# CONNECTROS.net
KiCad netlist of a schematic drawn in Altium Designer
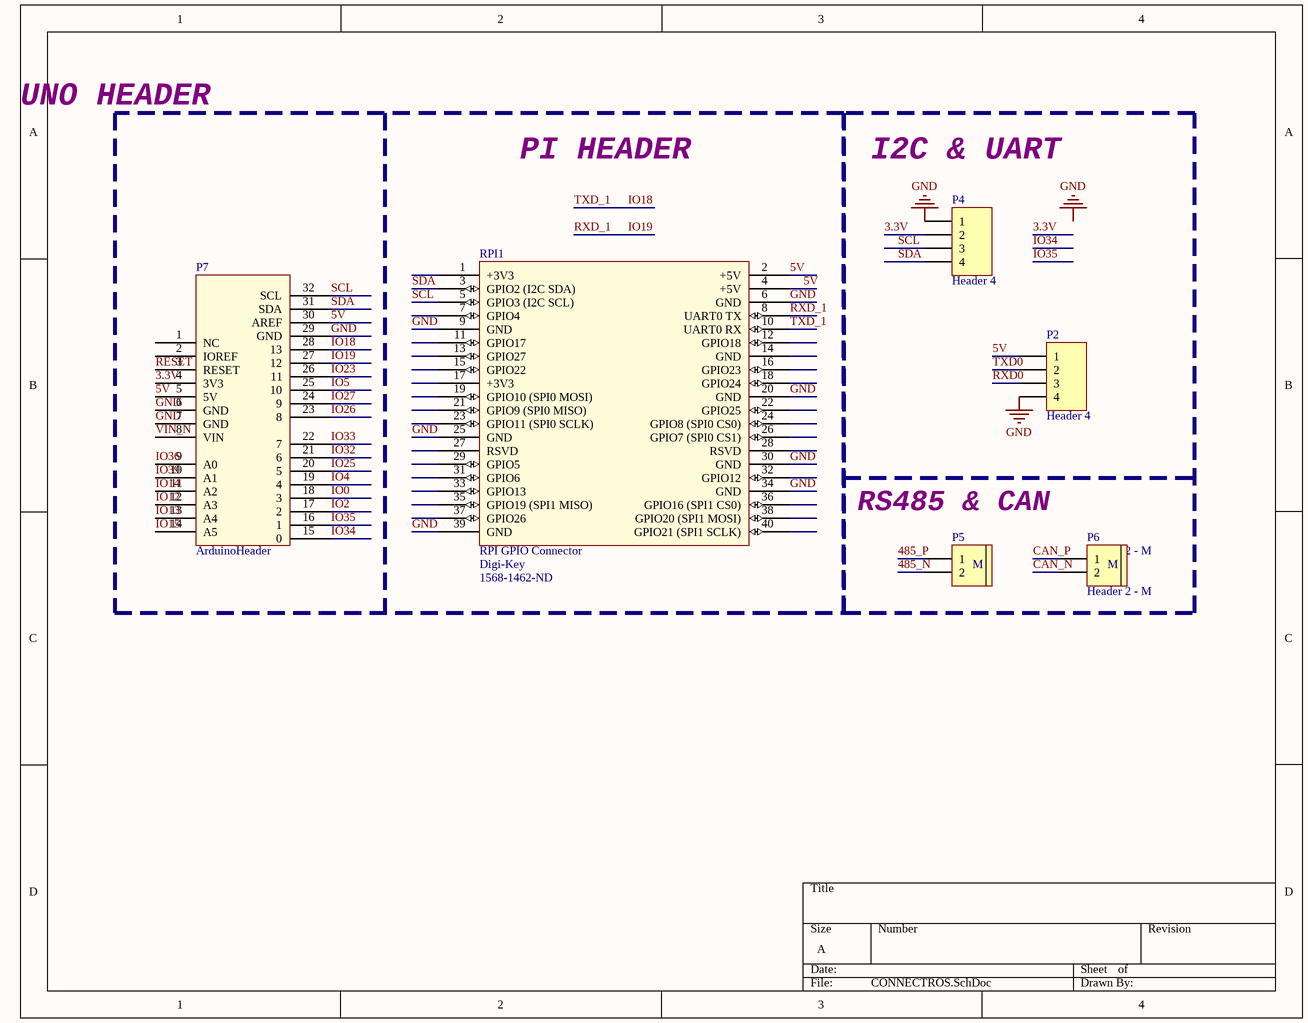
[diagram p0: CONNECTROS.SchDoc]

(export (version "E")
  (design (tool "Eeschema 10.0.6"))
  (components
    (comp (ref "P2")
      (value "Header 4")
      (footprint "HDR1X4")
      (description "Header, 4-Pin")
      (fields (field (name "PUBLISHER") "Altium Limited"))
      (libsource (lib "Miscellaneous Connectors") (part "Header 4"))
    )
    (comp (ref "P4")
      (value "Header 4")
      (footprint "CONN-TH_XH2.54-4AW")
      (description "Header, 4-Pin")
      (fields (field (name "PUBLISHER") "Altium Limited"))
      (libsource (lib "Miscellaneous Connectors") (part "Header 4"))
    )
    (comp (ref "P5")
      (value "Header 2 - M")
      (footprint "Medium - Header 2")
      (description "Header, 2-Pin, Medium")
      (fields (field (name "PUBLISHER") "Altium Limited"))
      (libsource (lib "My Library") (part "Header 2 - M"))
    )
    (comp (ref "P6")
      (value "Header 2 - M")
      (footprint "Medium - Header 2")
      (description "Header, 2-Pin, Medium")
      (fields (field (name "PUBLISHER") "Altium Limited"))
      (libsource (lib "My Library") (part "Header 2 - M"))
    )
    (comp (ref "P7")
      (value "ArduinoHeader")
      (footprint "ArduinoClone2")
      (libsource (lib "electronpowered") (part "ArduinoHeader"))
    )
    (comp (ref "RPI1")
      (value "RPI GPIO Connector")
      (footprint "rpi")
      (description "GPIO Header for Raspberry Pi A+/B+/Pi 2/Pi 3 - 2x20")
      (fields
        (field (name "MANUFACTURER") "SparkFun Electronics")
        (field (name "MANUFACTURER PART NUMBER") "PRT-14017")
        (field (name "SUPPLIER 1") "Digi-Key")
        (field (name "SUPPLIER PART NUMBER 1") "1568-1462-ND")
      )
      (libsource (lib "rpi") (part "rpi connector"))
    )
  )
  (nets
    (net (code "1") (name "/3.3V") (class "Default")
      (node (ref "P4") (pin "2") (pinfunction "2_2") (pintype "passive"))
      (node (ref "P7") (pin "4") (pinfunction "3V3_4") (pintype "passive"))
    )
    (net (code "2") (name "/5V") (class "Default")
      (node (ref "P2") (pin "1") (pinfunction "1_1") (pintype "passive"))
      (node (ref "P7") (pin "30") (pinfunction "AREF_30") (pintype "passive"))
      (node (ref "P7") (pin "5") (pinfunction "5V_5") (pintype "passive"))
      (node (ref "RPI1") (pin "2") (pinfunction "+5V_2") (pintype "power_in"))
      (node (ref "RPI1") (pin "4") (pinfunction "+5V_4") (pintype "power_in"))
    )
    (net (code "3") (name "/485_N") (class "Default")
      (node (ref "P5") (pin "2") (pinfunction "2_2") (pintype "passive"))
    )
    (net (code "4") (name "/485_P") (class "Default")
      (node (ref "P5") (pin "1") (pinfunction "1_1") (pintype "passive"))
    )
    (net (code "5") (name "/CAN_N") (class "Default")
      (node (ref "P6") (pin "2") (pinfunction "2_2") (pintype "passive"))
    )
    (net (code "6") (name "/CAN_P") (class "Default")
      (node (ref "P6") (pin "1") (pinfunction "1_1") (pintype "passive"))
    )
    (net (code "7") (name "/IO0") (class "Default")
      (node (ref "P7") (pin "18") (pinfunction "3_18") (pintype "passive"))
    )
    (net (code "8") (name "/IO2") (class "Default")
      (node (ref "P7") (pin "17") (pinfunction "2_17") (pintype "passive"))
    )
    (net (code "9") (name "/IO4") (class "Default")
      (node (ref "P7") (pin "19") (pinfunction "4_19") (pintype "passive"))
    )
    (net (code "10") (name "/IO5") (class "Default")
      (node (ref "P7") (pin "25") (pinfunction "10_25") (pintype "passive"))
    )
    (net (code "11") (name "/IO12") (class "Default")
      (node (ref "P7") (pin "12") (pinfunction "A3_12") (pintype "passive"))
    )
    (net (code "12") (name "/IO13") (class "Default")
      (node (ref "P7") (pin "13") (pinfunction "A4_13") (pintype "passive"))
    )
    (net (code "13") (name "/IO14") (class "Default")
      (node (ref "P7") (pin "11") (pinfunction "A2_11") (pintype "passive"))
    )
    (net (code "14") (name "/IO15") (class "Default")
      (node (ref "P7") (pin "14") (pinfunction "A5_14") (pintype "passive"))
    )
    (net (code "15") (name "/IO18") (class "Default")
      (node (ref "P7") (pin "28") (pinfunction "13_28") (pintype "passive"))
      (node (ref "RPI1") (pin "10") (pinfunction "UART0_RX_10") (pintype "bidirectional"))
    )
    (net (code "16") (name "/IO19") (class "Default")
      (node (ref "P7") (pin "27") (pinfunction "12_27") (pintype "passive"))
      (node (ref "RPI1") (pin "8") (pinfunction "UART0_TX_8") (pintype "bidirectional"))
    )
    (net (code "17") (name "/IO23") (class "Default")
      (node (ref "P7") (pin "26") (pinfunction "11_26") (pintype "passive"))
    )
    (net (code "18") (name "/IO25") (class "Default")
      (node (ref "P7") (pin "20") (pinfunction "5_20") (pintype "passive"))
    )
    (net (code "19") (name "/IO26") (class "Default")
      (node (ref "P7") (pin "23") (pinfunction "8_23") (pintype "passive"))
    )
    (net (code "20") (name "/IO27") (class "Default")
      (node (ref "P7") (pin "24") (pinfunction "9_24") (pintype "passive"))
    )
    (net (code "21") (name "/IO32") (class "Default")
      (node (ref "P7") (pin "21") (pinfunction "6_21") (pintype "passive"))
    )
    (net (code "22") (name "/IO33") (class "Default")
      (node (ref "P7") (pin "22") (pinfunction "7_22") (pintype "passive"))
    )
    (net (code "23") (name "/IO34") (class "Default")
      (node (ref "P7") (pin "15") (pinfunction "0_15") (pintype "passive"))
    )
    (net (code "24") (name "/IO35") (class "Default")
      (node (ref "P7") (pin "16") (pinfunction "1_16") (pintype "passive"))
    )
    (net (code "25") (name "/IO36") (class "Default")
      (node (ref "P7") (pin "9") (pinfunction "A0_9") (pintype "passive"))
    )
    (net (code "26") (name "/IO39") (class "Default")
      (node (ref "P7") (pin "10") (pinfunction "A1_10") (pintype "passive"))
    )
    (net (code "27") (name "/RESET") (class "Default")
      (node (ref "P7") (pin "3") (pinfunction "RESET_3") (pintype "passive"))
    )
    (net (code "28") (name "/RXD0") (class "Default")
      (node (ref "P2") (pin "3") (pinfunction "3_3") (pintype "passive"))
    )
    (net (code "29") (name "/SCL") (class "Default")
      (node (ref "P4") (pin "3") (pinfunction "3_3") (pintype "passive"))
      (node (ref "P7") (pin "32") (pinfunction "SCL_32") (pintype "passive"))
      (node (ref "RPI1") (pin "5") (pinfunction "GPIO3_(I2C_SCL)_5") (pintype "bidirectional"))
    )
    (net (code "30") (name "/SDA") (class "Default")
      (node (ref "P4") (pin "4") (pinfunction "4_4") (pintype "passive"))
      (node (ref "P7") (pin "31") (pinfunction "SDA_31") (pintype "passive"))
      (node (ref "RPI1") (pin "3") (pinfunction "GPIO2_(I2C_SDA)_3") (pintype "bidirectional"))
    )
    (net (code "31") (name "/TXD0") (class "Default")
      (node (ref "P2") (pin "2") (pinfunction "2_2") (pintype "passive"))
    )
    (net (code "32") (name "/VIN_N") (class "Default")
      (node (ref "P7") (pin "8") (pinfunction "VIN_8") (pintype "passive"))
    )
    (net (code "33") (name "GND") (class "Default")
      (node (ref "P2") (pin "4") (pinfunction "4_4") (pintype "passive"))
      (node (ref "P4") (pin "1") (pinfunction "1_1") (pintype "passive"))
      (node (ref "P7") (pin "29") (pinfunction "GND_29") (pintype "passive"))
      (node (ref "P7") (pin "6") (pinfunction "GND_6") (pintype "passive"))
      (node (ref "P7") (pin "7") (pinfunction "GND_7") (pintype "passive"))
      (node (ref "RPI1") (pin "20") (pinfunction "GND_20") (pintype "power_in"))
      (node (ref "RPI1") (pin "25") (pinfunction "GND_25") (pintype "power_in"))
      (node (ref "RPI1") (pin "30") (pinfunction "GND_30") (pintype "power_in"))
      (node (ref "RPI1") (pin "34") (pinfunction "GND_34") (pintype "passive"))
      (node (ref "RPI1") (pin "39") (pinfunction "GND_39") (pintype "power_in"))
      (node (ref "RPI1") (pin "6") (pinfunction "GND_6") (pintype "power_in"))
      (node (ref "RPI1") (pin "9") (pinfunction "GND_9") (pintype "power_in"))
    )
    (net (code "34") (name "unconnected-(P7-IOREF-Pad2)") (class "Default")
      (node (ref "P7") (pin "2") (pinfunction "IOREF_2") (pintype "passive"))
    )
    (net (code "35") (name "unconnected-(P7-NC-Pad1)") (class "Default")
      (node (ref "P7") (pin "1") (pinfunction "NC_1") (pintype "passive"))
    )
    (net (code "36") (name "unconnected-(RPI1-+3V3-Pad1)") (class "Default")
      (node (ref "RPI1") (pin "1") (pinfunction "+3V3_1") (pintype "power_in"))
    )
    (net (code "37") (name "unconnected-(RPI1-+3V3-Pad17)") (class "Default")
      (node (ref "RPI1") (pin "17") (pinfunction "+3V3_17") (pintype "power_in"))
    )
    (net (code "38") (name "unconnected-(RPI1-GND-Pad14)") (class "Default")
      (node (ref "RPI1") (pin "14") (pinfunction "GND_14") (pintype "power_in"))
    )
    (net (code "39") (name "unconnected-(RPI1-GPIO4-Pad7)") (class "Default")
      (node (ref "RPI1") (pin "7") (pinfunction "GPIO4_7") (pintype "bidirectional"))
    )
    (net (code "40") (name "unconnected-(RPI1-GPIO5-Pad29)") (class "Default")
      (node (ref "RPI1") (pin "29") (pinfunction "GPIO5_29") (pintype "bidirectional"))
    )
    (net (code "41") (name "unconnected-(RPI1-GPIO6-Pad31)") (class "Default")
      (node (ref "RPI1") (pin "31") (pinfunction "GPIO6_31") (pintype "bidirectional"))
    )
    (net (code "42") (name "unconnected-(RPI1-GPIO7_(SPI0_CS1)-Pad26)") (class "Default")
      (node (ref "RPI1") (pin "26") (pinfunction "GPIO7_(SPI0_CS1)_26") (pintype "bidirectional"))
    )
    (net (code "43") (name "unconnected-(RPI1-GPIO8_(SPI0_CS0)-Pad24)") (class "Default")
      (node (ref "RPI1") (pin "24") (pinfunction "GPIO8_(SPI0_CS0)_24") (pintype "bidirectional"))
    )
    (net (code "44") (name "unconnected-(RPI1-GPIO9_(SPI0_MISO)-Pad21)") (class "Default")
      (node (ref "RPI1") (pin "21") (pinfunction "GPIO9_(SPI0_MISO)_21") (pintype "bidirectional"))
    )
    (net (code "45") (name "unconnected-(RPI1-GPIO10_(SPI0_MOSI)-Pad19)") (class "Default")
      (node (ref "RPI1") (pin "19") (pinfunction "GPIO10_(SPI0_MOSI)_19") (pintype "bidirectional"))
    )
    (net (code "46") (name "unconnected-(RPI1-GPIO11_(SPI0_SCLK)-Pad23)") (class "Default")
      (node (ref "RPI1") (pin "23") (pinfunction "GPIO11_(SPI0_SCLK)_23") (pintype "bidirectional"))
    )
    (net (code "47") (name "unconnected-(RPI1-GPIO12-Pad32)") (class "Default")
      (node (ref "RPI1") (pin "32") (pinfunction "GPIO12_32") (pintype "bidirectional"))
    )
    (net (code "48") (name "unconnected-(RPI1-GPIO13-Pad33)") (class "Default")
      (node (ref "RPI1") (pin "33") (pinfunction "GPIO13_33") (pintype "bidirectional"))
    )
    (net (code "49") (name "unconnected-(RPI1-GPIO16_(SPI1_CS0)-Pad36)") (class "Default")
      (node (ref "RPI1") (pin "36") (pinfunction "GPIO16_(SPI1_CS0)_36") (pintype "bidirectional"))
    )
    (net (code "50") (name "unconnected-(RPI1-GPIO17-Pad11)") (class "Default")
      (node (ref "RPI1") (pin "11") (pinfunction "GPIO17_11") (pintype "bidirectional"))
    )
    (net (code "51") (name "unconnected-(RPI1-GPIO18-Pad12)") (class "Default")
      (node (ref "RPI1") (pin "12") (pinfunction "GPIO18_12") (pintype "bidirectional"))
    )
    (net (code "52") (name "unconnected-(RPI1-GPIO19_(SPI1_MISO)-Pad35)") (class "Default")
      (node (ref "RPI1") (pin "35") (pinfunction "GPIO19_(SPI1_MISO)_35") (pintype "bidirectional"))
    )
    (net (code "53") (name "unconnected-(RPI1-GPIO20_(SPI1_MOSI)-Pad38)") (class "Default")
      (node (ref "RPI1") (pin "38") (pinfunction "GPIO20_(SPI1_MOSI)_38") (pintype "bidirectional"))
    )
    (net (code "54") (name "unconnected-(RPI1-GPIO21_(SPI1_SCLK)-Pad40)") (class "Default")
      (node (ref "RPI1") (pin "40") (pinfunction "GPIO21_(SPI1_SCLK)_40") (pintype "bidirectional"))
    )
    (net (code "55") (name "unconnected-(RPI1-GPIO22-Pad15)") (class "Default")
      (node (ref "RPI1") (pin "15") (pinfunction "GPIO22_15") (pintype "bidirectional"))
    )
    (net (code "56") (name "unconnected-(RPI1-GPIO23-Pad16)") (class "Default")
      (node (ref "RPI1") (pin "16") (pinfunction "GPIO23_16") (pintype "bidirectional"))
    )
    (net (code "57") (name "unconnected-(RPI1-GPIO24-Pad18)") (class "Default")
      (node (ref "RPI1") (pin "18") (pinfunction "GPIO24_18") (pintype "bidirectional"))
    )
    (net (code "58") (name "unconnected-(RPI1-GPIO25-Pad22)") (class "Default")
      (node (ref "RPI1") (pin "22") (pinfunction "GPIO25_22") (pintype "bidirectional"))
    )
    (net (code "59") (name "unconnected-(RPI1-GPIO26-Pad37)") (class "Default")
      (node (ref "RPI1") (pin "37") (pinfunction "GPIO26_37") (pintype "bidirectional"))
    )
    (net (code "60") (name "unconnected-(RPI1-GPIO27-Pad13)") (class "Default")
      (node (ref "RPI1") (pin "13") (pinfunction "GPIO27_13") (pintype "bidirectional"))
    )
    (net (code "61") (name "unconnected-(RPI1-RSVD-Pad27)") (class "Default")
      (node (ref "RPI1") (pin "27") (pinfunction "RSVD_27") (pintype "passive"))
    )
    (net (code "62") (name "unconnected-(RPI1-RSVD-Pad28)") (class "Default")
      (node (ref "RPI1") (pin "28") (pinfunction "RSVD_28") (pintype "passive"))
    )
  )
)
